# SparkFun_Artemis_OpenLog.net
KiCad netlist of a schematic drawn in EAGLE
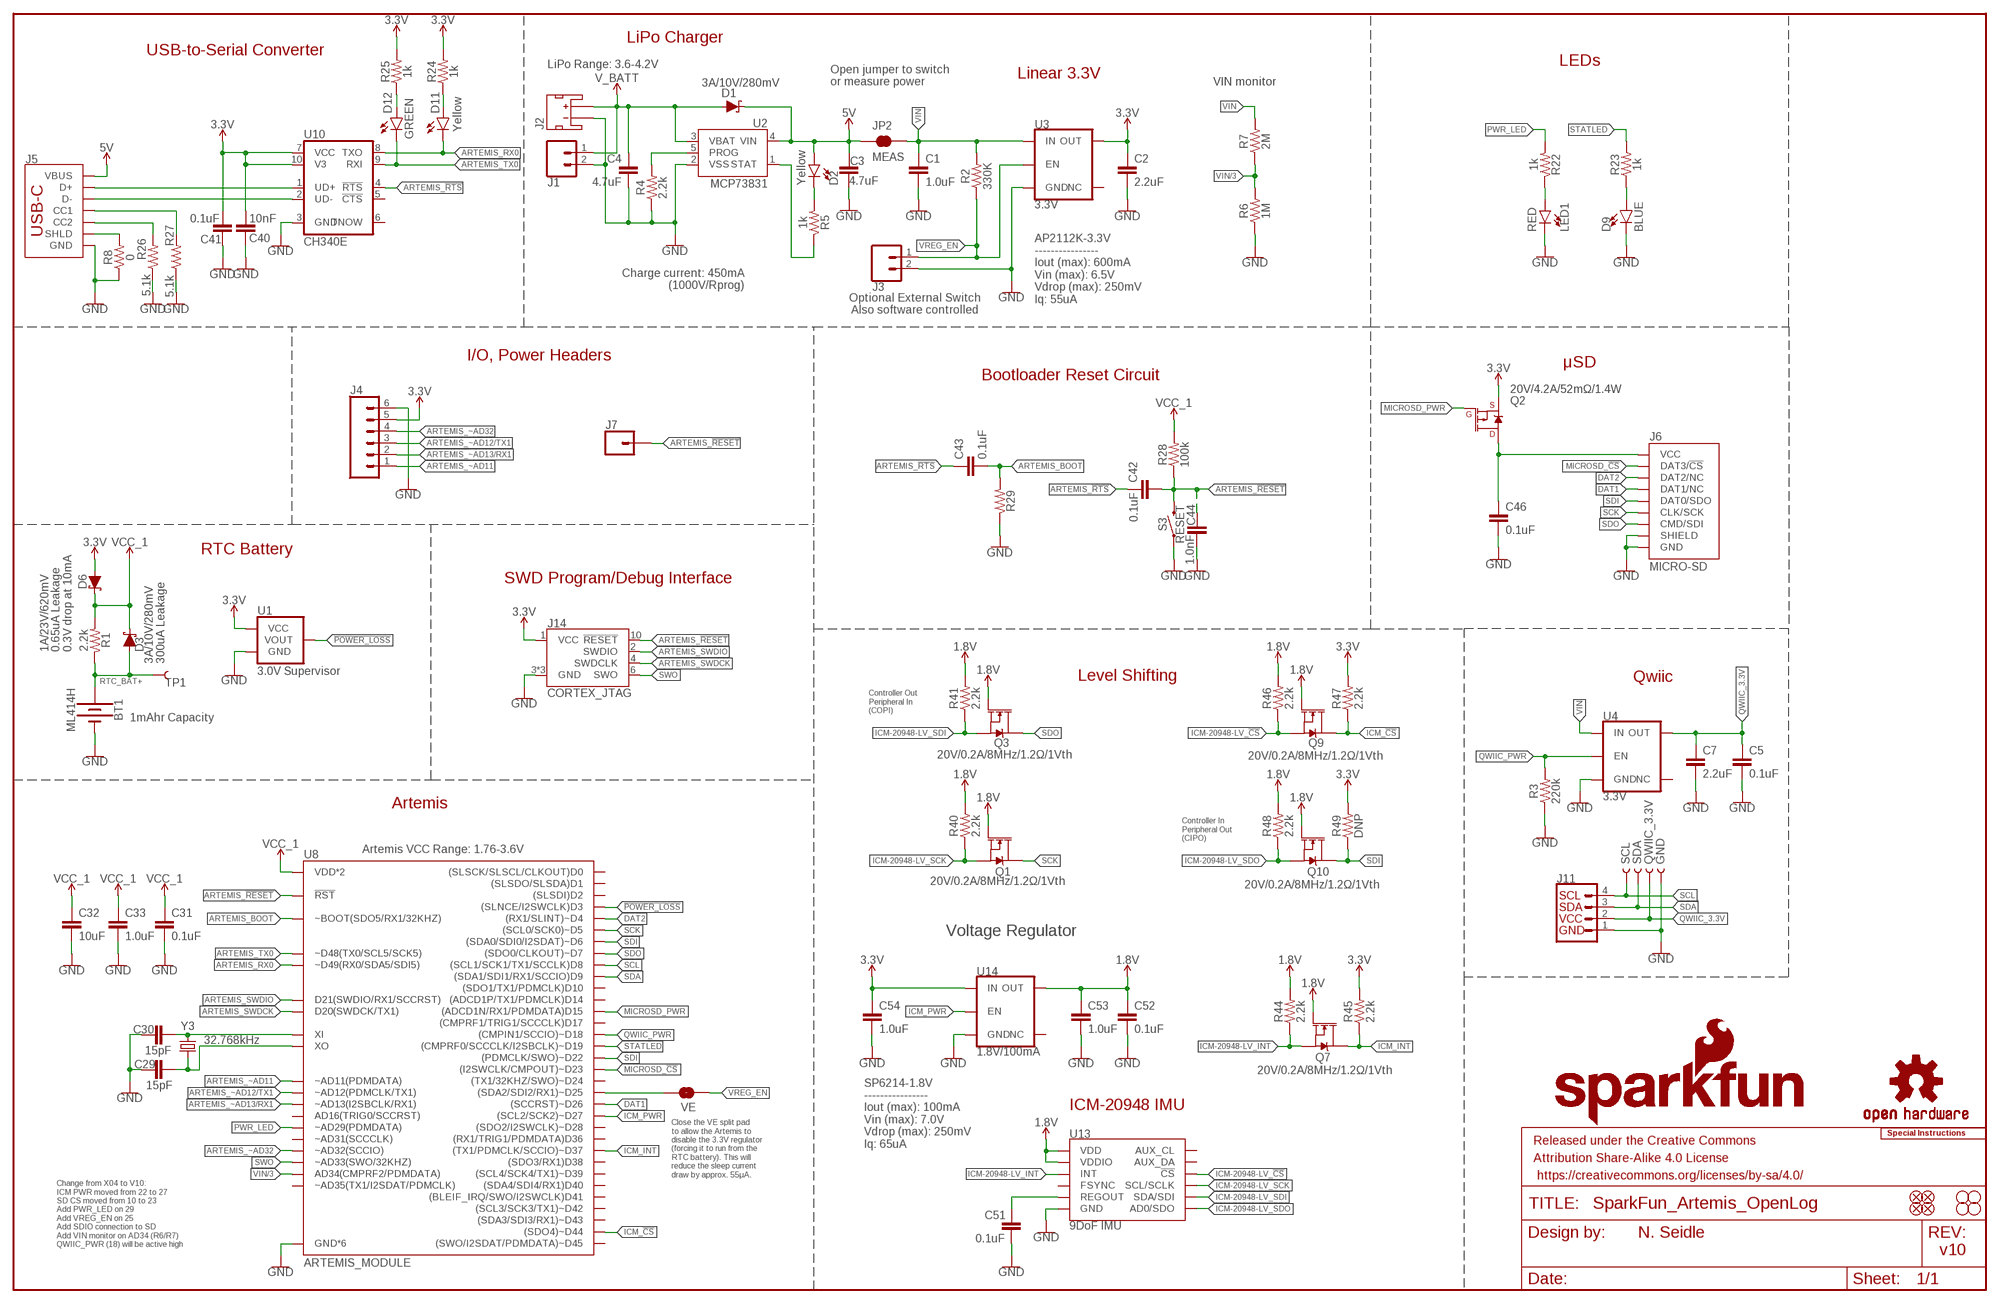
[diagram p0: schematic, sheet 1]

(export (version "E")
  (design (tool "Eeschema 10.0.6"))
  (components
    (comp (ref "BT1")
      (value "ML414H")
      (footprint "eagle-import:ML414H_IV01E")
      (libsource (lib "eagle-import") (part "ML414H_IV01E_BATTERY"))
    )
    (comp (ref "C1")
      (value "1.0uF")
      (footprint "eagle-import:0402-TIGHT")
      (libsource (lib "eagle-import") (part "1.0UF-0402T-16V-10%"))
    )
    (comp (ref "C2")
      (value "2.2uF")
      (footprint "eagle-import:0402-TIGHT")
      (libsource (lib "eagle-import") (part "2.2UF-0402_TIGHT-10V-10%-X5R"))
    )
    (comp (ref "C3")
      (value "4.7uF")
      (footprint "eagle-import:0402-TIGHT")
      (libsource (lib "eagle-import") (part "4.7UF-0402_TIGHT-6.3V-20%-X5R"))
    )
    (comp (ref "C4")
      (value "4.7uF")
      (footprint "eagle-import:0402-TIGHT")
      (libsource (lib "eagle-import") (part "4.7UF-0402_TIGHT-6.3V-20%-X5R"))
    )
    (comp (ref "C5")
      (value "0.1uF")
      (footprint "eagle-import:0402-TIGHT")
      (libsource (lib "eagle-import") (part "0.1UF-0402T-6.3V-10%-X7R"))
    )
    (comp (ref "C7")
      (value "2.2uF")
      (footprint "eagle-import:0402-TIGHT")
      (libsource (lib "eagle-import") (part "2.2UF-0402_TIGHT-10V-10%-X5R"))
    )
    (comp (ref "C29")
      (value "15pF")
      (footprint "eagle-import:0402-TIGHT")
      (libsource (lib "eagle-import") (part "15PF-0402T-50V-5%"))
    )
    (comp (ref "C30")
      (value "15pF")
      (footprint "eagle-import:0402-TIGHT")
      (libsource (lib "eagle-import") (part "15PF-0402T-50V-5%"))
    )
    (comp (ref "C31")
      (value "0.1uF")
      (footprint "eagle-import:0402-TIGHT")
      (libsource (lib "eagle-import") (part "0.1UF-0402T-16V-10%"))
    )
    (comp (ref "C32")
      (value "10uF")
      (footprint "eagle-import:0402-TIGHT")
      (libsource (lib "eagle-import") (part "10UF-0402T-6.3V-20%"))
    )
    (comp (ref "C33")
      (value "1.0uF")
      (footprint "eagle-import:0402-TIGHT")
      (libsource (lib "eagle-import") (part "1.0UF-0402T-16V-10%"))
    )
    (comp (ref "C40")
      (value "10nF")
      (footprint "eagle-import:0402-TIGHT")
      (libsource (lib "eagle-import") (part "10NF-0402T-25V-10%"))
    )
    (comp (ref "C41")
      (value "0.1uF")
      (footprint "eagle-import:0402-TIGHT")
      (libsource (lib "eagle-import") (part "0.1UF-0402T-16V-10%"))
    )
    (comp (ref "C42")
      (value "0.1uF")
      (footprint "eagle-import:0402-TIGHT")
      (libsource (lib "eagle-import") (part "0.1UF-0402T-16V-10%"))
    )
    (comp (ref "C43")
      (value "0.1uF")
      (footprint "eagle-import:0402-TIGHT")
      (libsource (lib "eagle-import") (part "0.1UF-0402T-16V-10%"))
    )
    (comp (ref "C44")
      (value "1.0nF")
      (footprint "eagle-import:0402-TIGHT")
      (libsource (lib "eagle-import") (part "1.0NF/1000PF-0402_TIGHT-50V-10%"))
    )
    (comp (ref "C46")
      (value "0.1uF")
      (footprint "eagle-import:0402-TIGHT")
      (libsource (lib "eagle-import") (part "0.1UF-0402T-16V-10%"))
    )
    (comp (ref "C51")
      (value "0.1uF")
      (footprint "eagle-import:0402-TIGHT")
      (libsource (lib "eagle-import") (part "0.1UF-0402T-16V-10%"))
    )
    (comp (ref "C52")
      (value "0.1uF")
      (footprint "eagle-import:0402-TIGHT")
      (libsource (lib "eagle-import") (part "0.1UF-0402T-16V-10%"))
    )
    (comp (ref "C53")
      (value "1.0uF")
      (footprint "eagle-import:0402-TIGHT")
      (libsource (lib "eagle-import") (part "1.0UF-0402T-16V-10%"))
    )
    (comp (ref "C54")
      (value "1.0uF")
      (footprint "eagle-import:0402-TIGHT")
      (libsource (lib "eagle-import") (part "1.0UF-0402T-16V-10%"))
    )
    (comp (ref "D1")
      (value "3A/10V/280mV")
      (footprint "eagle-import:SOD-323")
      (libsource (lib "eagle-import") (part "DIODE-SCHOTTKY-BAT60A"))
    )
    (comp (ref "D2")
      (value "Yellow")
      (footprint "eagle-import:LED-0603")
      (libsource (lib "eagle-import") (part "LED-YELLOW0603"))
    )
    (comp (ref "D3")
      (value "3A/10V/280mV")
      (footprint "eagle-import:SOD-323")
      (libsource (lib "eagle-import") (part "DIODE-SCHOTTKY-BAT60A"))
    )
    (comp (ref "D6")
      (value "1A/23V/620mV")
      (footprint "eagle-import:SOD-323")
      (libsource (lib "eagle-import") (part "DIODE-SCHOTTKY-BAT20J"))
    )
    (comp (ref "D9")
      (value "BLUE")
      (footprint "eagle-import:LED-0603")
      (libsource (lib "eagle-import") (part "LED-BLUE0603"))
    )
    (comp (ref "D11")
      (value "Yellow")
      (footprint "eagle-import:LED-0603")
      (libsource (lib "eagle-import") (part "LED-YELLOW0603"))
    )
    (comp (ref "D12")
      (value "GREEN")
      (footprint "eagle-import:LED-0603")
      (libsource (lib "eagle-import") (part "LED-GREEN0603"))
    )
    (comp (ref "FD1")
      (value "FIDUCIAL1X2")
      (footprint "eagle-import:FIDUCIAL-1X2")
      (libsource (lib "eagle-import") (part "FIDUCIAL1X2"))
    )
    (comp (ref "FD2")
      (value "FIDUCIAL1X2")
      (footprint "eagle-import:FIDUCIAL-1X2")
      (libsource (lib "eagle-import") (part "FIDUCIAL1X2"))
    )
    (comp (ref "FD3")
      (value "FIDUCIAL1X2")
      (footprint "eagle-import:FIDUCIAL-1X2")
      (libsource (lib "eagle-import") (part "FIDUCIAL1X2"))
    )
    (comp (ref "FD4")
      (value "FIDUCIAL1X2")
      (footprint "eagle-import:FIDUCIAL-1X2")
      (libsource (lib "eagle-import") (part "FIDUCIAL1X2"))
    )
    (comp (ref "FRAME1")
      (value "FRAME-LEDGER")
      (footprint "eagle-import:CREATIVE_COMMONS")
      (libsource (lib "eagle-import") (part "FRAME-LEDGER"))
    )
    (comp (ref "GND")
      (value "TEST-POINTTP_15TH_THRU")
      (footprint "eagle-import:TP_15TH")
      (libsource (lib "eagle-import") (part "TEST-POINTTP_15TH_THRU"))
    )
    (comp (ref "H1")
      (value "STAND-OFF")
      (footprint "eagle-import:STAND-OFF")
      (libsource (lib "eagle-import") (part "STAND-OFF"))
    )
    (comp (ref "H2")
      (value "STAND-OFF")
      (footprint "eagle-import:STAND-OFF")
      (libsource (lib "eagle-import") (part "STAND-OFF"))
    )
    (comp (ref "H3")
      (value "STAND-OFF")
      (footprint "eagle-import:STAND-OFF")
      (libsource (lib "eagle-import") (part "STAND-OFF"))
    )
    (comp (ref "H4")
      (value "STAND-OFF")
      (footprint "eagle-import:STAND-OFF")
      (libsource (lib "eagle-import") (part "STAND-OFF"))
    )
    (comp (ref "J1")
      (value "CONN_021X02_NO_SILK")
      (footprint "eagle-import:1X02_NO_SILK")
      (libsource (lib "eagle-import") (part "CONN_021X02_NO_SILK"))
    )
    (comp (ref "J2")
      (value "JST_2MM_MALE")
      (footprint "eagle-import:JST-2-SMD")
      (libsource (lib "eagle-import") (part "JST_2MM_MALE"))
    )
    (comp (ref "J3")
      (value "CONN_021X02_NO_SILK")
      (footprint "eagle-import:1X02_NO_SILK")
      (libsource (lib "eagle-import") (part "CONN_021X02_NO_SILK"))
    )
    (comp (ref "J4")
      (value "CONN_06NO_SILK_NO_POP")
      (footprint "eagle-import:1X06_NO_SILK")
      (libsource (lib "eagle-import") (part "CONN_06NO_SILK_NO_POP"))
    )
    (comp (ref "J5")
      (value "USB_C_4-LAYER_PADS")
      (footprint "eagle-import:USB-C-16P_4LAYER-PADS")
      (libsource (lib "eagle-import") (part "USB_C_4-LAYER_PADS"))
    )
    (comp (ref "J6")
      (value "MICRO-SD")
      (footprint "eagle-import:MICRO-SD-SOCKET")
      (libsource (lib "eagle-import") (part "MICRO-SD-SDIOPUSH-PUSH"))
    )
    (comp (ref "J7")
      (value "CONN_01PTH_NO_SILK_YES_STOP")
      (footprint "eagle-import:1X01_NO_SILK")
      (libsource (lib "eagle-import") (part "CONN_01PTH_NO_SILK_YES_STOP"))
    )
    (comp (ref "J11")
      (value "QWIIC_CONNECTORJS-1MM")
      (footprint "eagle-import:JST04_1MM_RA")
      (libsource (lib "eagle-import") (part "QWIIC_CONNECTORJS-1MM"))
    )
    (comp (ref "J14")
      (value "CORTEX_JTAG")
      (footprint "eagle-import:2X5-PTH-1.27MM")
      (libsource (lib "eagle-import") (part "CORTEX_JTAG_DEBUG_MINIMUM_PTH"))
    )
    (comp (ref "JP2")
      (value "MEAS")
      (footprint "eagle-import:COMBO-JUMPER_2_NC_TRACE")
      (libsource (lib "eagle-import") (part "JUMPER-COMBO_2_NC_TRACE"))
    )
    (comp (ref "LED1")
      (value "RED")
      (footprint "eagle-import:LED-0603")
      (libsource (lib "eagle-import") (part "LED-RED0603"))
    )
    (comp (ref "LOGO1")
      (value "SFE_LOGO_NAME.1_INCH")
      (footprint "eagle-import:SFE_LOGO_NAME_.1")
      (libsource (lib "eagle-import") (part "SFE_LOGO_NAME.1_INCH"))
    )
    (comp (ref "LOGO2")
      (value "OSHW-LOGOS")
      (footprint "eagle-import:OSHW-LOGO-S")
      (libsource (lib "eagle-import") (part "OSHW-LOGOS"))
    )
    (comp (ref "LOGO3")
      (value "SPECIAL_INSTRUCTIONS-ORDERING")
      (footprint "eagle-import:ORDERING_INSTRUCTIONS")
      (libsource (lib "eagle-import") (part "SPECIAL_INSTRUCTIONS-ORDERING"))
    )
    (comp (ref "LOGO4")
      (value "SFE_LOGO_FLAME.1_INCH")
      (footprint "eagle-import:SFE_LOGO_FLAME_.1")
      (libsource (lib "eagle-import") (part "SFE_LOGO_FLAME.1_INCH"))
    )
    (comp (ref "LOGO5")
      (value "SFE_LOGO_FLAME.1_INCH")
      (footprint "eagle-import:SFE_LOGO_FLAME_.1")
      (libsource (lib "eagle-import") (part "SFE_LOGO_FLAME.1_INCH"))
    )
    (comp (ref "Q1")
      (value "20V/0.2A/8MHz/1.2Ω/1Vth")
      (footprint "eagle-import:SOT-416FL")
      (libsource (lib "eagle-import") (part "MOSFET-NCH-RE1C00UNTL"))
    )
    (comp (ref "Q2")
      (value "20V/4.2A/52mΩ/1.4W")
      (footprint "eagle-import:SOT23-3")
      (libsource (lib "eagle-import") (part "MOSFET_PCH-DMG2305UX-7"))
    )
    (comp (ref "Q3")
      (value "20V/0.2A/8MHz/1.2Ω/1Vth")
      (footprint "eagle-import:SOT-416FL")
      (libsource (lib "eagle-import") (part "MOSFET-NCH-RE1C00UNTL"))
    )
    (comp (ref "Q7")
      (value "20V/0.2A/8MHz/1.2Ω/1Vth")
      (footprint "eagle-import:SOT-416FL")
      (libsource (lib "eagle-import") (part "MOSFET-NCH-RE1C00UNTL"))
    )
    (comp (ref "Q9")
      (value "20V/0.2A/8MHz/1.2Ω/1Vth")
      (footprint "eagle-import:SOT-416FL")
      (libsource (lib "eagle-import") (part "MOSFET-NCH-RE1C00UNTL"))
    )
    (comp (ref "Q10")
      (value "20V/0.2A/8MHz/1.2Ω/1Vth")
      (footprint "eagle-import:SOT-416FL")
      (libsource (lib "eagle-import") (part "MOSFET-NCH-RE1C00UNTL"))
    )
    (comp (ref "QWIIC_3.3V")
      (value "TEST-POINTTP_15TH_THRU")
      (footprint "eagle-import:TP_15TH")
      (libsource (lib "eagle-import") (part "TEST-POINTTP_15TH_THRU"))
    )
    (comp (ref "R1")
      (value "2.2k")
      (footprint "eagle-import:0402-TIGHT")
      (libsource (lib "eagle-import") (part "2.2KOHM-0402T-1/16W-1%"))
    )
    (comp (ref "R2")
      (value "330K")
      (footprint "eagle-import:0402-TIGHT")
      (libsource (lib "eagle-import") (part "330KOHM-0402T-1/16W-1%"))
    )
    (comp (ref "R3")
      (value "220k")
      (footprint "eagle-import:0402-TIGHT")
      (libsource (lib "eagle-import") (part "220KOHM-0402T-1/16W-1%"))
    )
    (comp (ref "R4")
      (value "2.2k")
      (footprint "eagle-import:0402-TIGHT")
      (libsource (lib "eagle-import") (part "2.2KOHM-0402T-1/16W-1%"))
    )
    (comp (ref "R5")
      (value "1k")
      (footprint "eagle-import:0402-TIGHT")
      (libsource (lib "eagle-import") (part "1KOHM-0402T-1/16W-1%"))
    )
    (comp (ref "R6")
      (value "1M")
      (footprint "eagle-import:0402-TIGHT")
      (libsource (lib "eagle-import") (part "1MOHM-0402T-1/16W-1%"))
    )
    (comp (ref "R7")
      (value "2M")
      (footprint "eagle-import:0402-TIGHT")
      (libsource (lib "eagle-import") (part "2MOHM-0402T-1/16W-1%"))
    )
    (comp (ref "R8")
      (value "0")
      (footprint "eagle-import:0402-TIGHT")
      (libsource (lib "eagle-import") (part "0OHM-0402T-1/10W"))
    )
    (comp (ref "R22")
      (value "1k")
      (footprint "eagle-import:0402-TIGHT")
      (libsource (lib "eagle-import") (part "1KOHM-0402T-1/16W-1%"))
    )
    (comp (ref "R23")
      (value "1k")
      (footprint "eagle-import:0402-TIGHT")
      (libsource (lib "eagle-import") (part "1KOHM-0402T-1/16W-1%"))
    )
    (comp (ref "R24")
      (value "1k")
      (footprint "eagle-import:0402-TIGHT")
      (libsource (lib "eagle-import") (part "1KOHM-0402T-1/16W-1%"))
    )
    (comp (ref "R25")
      (value "1k")
      (footprint "eagle-import:0402-TIGHT")
      (libsource (lib "eagle-import") (part "1KOHM-0402T-1/16W-1%"))
    )
    (comp (ref "R26")
      (value "5.1k")
      (footprint "eagle-import:0402-TIGHT")
      (libsource (lib "eagle-import") (part "5.1KOHM-0402T-1/16W-1%"))
    )
    (comp (ref "R27")
      (value "5.1k")
      (footprint "eagle-import:0402-TIGHT")
      (libsource (lib "eagle-import") (part "5.1KOHM-0402T-1/16W-1%"))
    )
    (comp (ref "R28")
      (value "100k")
      (footprint "eagle-import:0402-TIGHT")
      (libsource (lib "eagle-import") (part "100KOHM-0402T-1/16W-1%"))
    )
    (comp (ref "R29")
      (value "220KOHM-0402T-1/16W-1%")
      (footprint "eagle-import:0402-TIGHT")
      (libsource (lib "eagle-import") (part "220KOHM-0402T-1/16W-1%"))
    )
    (comp (ref "R40")
      (value "2.2k")
      (footprint "eagle-import:0402-TIGHT")
      (libsource (lib "eagle-import") (part "2.2KOHM-0402T-1/16W-1%"))
    )
    (comp (ref "R41")
      (value "2.2k")
      (footprint "eagle-import:0402-TIGHT")
      (libsource (lib "eagle-import") (part "2.2KOHM-0402T-1/16W-1%"))
    )
    (comp (ref "R44")
      (value "2.2k")
      (footprint "eagle-import:0402-TIGHT")
      (libsource (lib "eagle-import") (part "2.2KOHM-0402T-1/16W-1%"))
    )
    (comp (ref "R45")
      (value "2.2k")
      (footprint "eagle-import:0402-TIGHT")
      (libsource (lib "eagle-import") (part "2.2KOHM-0402T-1/16W-1%"))
    )
    (comp (ref "R46")
      (value "2.2k")
      (footprint "eagle-import:0402-TIGHT")
      (libsource (lib "eagle-import") (part "2.2KOHM-0402T-1/16W-1%"))
    )
    (comp (ref "R47")
      (value "2.2k")
      (footprint "eagle-import:0402-TIGHT")
      (libsource (lib "eagle-import") (part "2.2KOHM-0402T-1/16W-1%"))
    )
    (comp (ref "R48")
      (value "2.2k")
      (footprint "eagle-import:0402-TIGHT")
      (libsource (lib "eagle-import") (part "2.2KOHM-0402T-1/16W-1%"))
    )
    (comp (ref "R49")
      (value "DNP")
      (footprint "eagle-import:0402-TIGHT")
      (libsource (lib "eagle-import") (part "RESISTOR0402T"))
    )
    (comp (ref "S3")
      (value "RESET")
      (footprint "eagle-import:TACTILE_SWITCH_SMD_4.6X2.8MM")
      (libsource (lib "eagle-import") (part "MOMENTARY-SWITCH-SPST-SMD-4.6X2.8MM"))
    )
    (comp (ref "SCL")
      (value "TEST-POINTTP_15TH_THRU")
      (footprint "eagle-import:TP_15TH")
      (libsource (lib "eagle-import") (part "TEST-POINTTP_15TH_THRU"))
    )
    (comp (ref "SDA")
      (value "TEST-POINTTP_15TH_THRU")
      (footprint "eagle-import:TP_15TH")
      (libsource (lib "eagle-import") (part "TEST-POINTTP_15TH_THRU"))
    )
    (comp (ref "TP1")
      (value "TEST-POINT3")
      (footprint "eagle-import:PAD.03X.03")
      (libsource (lib "eagle-import") (part "TEST-POINT3"))
    )
    (comp (ref "U1")
      (value "3.0V Supervisor")
      (footprint "eagle-import:SOT23-3")
      (libsource (lib "eagle-import") (part "V_SUPERVISOR"))
    )
    (comp (ref "U2")
      (value "MCP73831")
      (footprint "eagle-import:SOT23-5")
      (libsource (lib "eagle-import") (part "MCP73831"))
    )
    (comp (ref "U3")
      (value "3.3V")
      (footprint "eagle-import:SOT23-5")
      (libsource (lib "eagle-import") (part "V_REG_AP2112K-3.3V"))
    )
    (comp (ref "U4")
      (value "3.3V")
      (footprint "eagle-import:SOT23-5")
      (libsource (lib "eagle-import") (part "V_REG_AP2112K-3.3V"))
    )
    (comp (ref "U8")
      (value "ARTEMIS_MODULE")
      (footprint "eagle-import:ARTEMIS_FP")
      (libsource (lib "eagle-import") (part "ARTEMIS_MODULESMD"))
    )
    (comp (ref "U10")
      (value "CH340E")
      (footprint "eagle-import:MSOP10")
      (libsource (lib "eagle-import") (part "CH340E_MSOP10"))
    )
    (comp (ref "U13")
      (value "9DoF IMU")
      (footprint "eagle-import:QFN24-3X3-ICM-20948")
      (libsource (lib "eagle-import") (part "ICM-20948"))
    )
    (comp (ref "U14")
      (value "1.8V/100mA")
      (footprint "eagle-import:SC70")
      (libsource (lib "eagle-import") (part "V_REG_SP6214-1.8V"))
    )
    (comp (ref "VE")
      (value "JUMPER-SMT_2_NO_SILK")
      (footprint "eagle-import:SMT-JUMPER_2_NO_SILK")
      (libsource (lib "eagle-import") (part "JUMPER-SMT_2_NO_SILK"))
    )
    (comp (ref "Y3")
      (value "32.768kHz")
      (footprint "eagle-import:CRYSTAL-SMD-3.2X1.5MM")
      (libsource (lib "eagle-import") (part "CRYSTAL-32.768KHZSMD-3.2X1.5"))
    )
  )
  (nets
    (net (code "1") (name "/ARTEMIS_~{AD11}") (class "Default")
      (node (ref "J4") (pin "1") (pinfunction "1_1") (pintype "passive"))
      (node (ref "U8") (pin "~AD11") (pinfunction "~{AD11(PDMDATA})_~AD11") (pintype "bidirectional"))
    )
    (net (code "2") (name "/ARTEMIS_~{AD12{slash}TX1}") (class "Default")
      (node (ref "J4") (pin "3") (pinfunction "3_3") (pintype "passive"))
      (node (ref "U8") (pin "~AD12") (pinfunction "~{AD12(PDMCLK/TX1})_~AD12") (pintype "bidirectional"))
    )
    (net (code "3") (name "/ARTEMIS_~{AD13{slash}RX1}") (class "Default")
      (node (ref "J4") (pin "2") (pinfunction "2_2") (pintype "passive"))
      (node (ref "U8") (pin "~AD13") (pinfunction "~{AD13(I2SBCLK/RX1})_~AD13") (pintype "bidirectional"))
    )
    (net (code "4") (name "/ARTEMIS_~{AD32}") (class "Default")
      (node (ref "J4") (pin "4") (pinfunction "4_4") (pintype "passive"))
      (node (ref "U8") (pin "~AD32") (pinfunction "~{AD32(SCCIO})_~AD32") (pintype "bidirectional"))
    )
    (net (code "5") (name "/ARTEMIS_~{RESET}") (class "Default")
      (node (ref "C42") (pin "2") (pinfunction "2_2") (pintype "passive"))
      (node (ref "C44") (pin "1") (pinfunction "1_1") (pintype "passive"))
      (node (ref "J14") (pin "10") (pinfunction "~{RESET}_10") (pintype "bidirectional"))
      (node (ref "J7") (pin "1") (pinfunction "1_1") (pintype "passive"))
      (node (ref "R28") (pin "1") (pinfunction "1_1") (pintype "passive"))
      (node (ref "S3") (pin "3") (pinfunction "2_3") (pintype "passive"))
      (node (ref "S3") (pin "4") (pinfunction "2_4") (pintype "passive"))
      (node (ref "U8") (pin "~RST") (pinfunction "~{RST}_~RST") (pintype "bidirectional"))
    )
    (net (code "6") (name "/ARTEMIS_~{RTS}") (class "Default")
      (node (ref "C42") (pin "1") (pinfunction "1_1") (pintype "passive"))
      (node (ref "C43") (pin "1") (pinfunction "1_1") (pintype "passive"))
      (node (ref "U10") (pin "4") (pinfunction "~{RTS}_4") (pintype "bidirectional"))
    )
    (net (code "7") (name "/ICM-20948-LV_~{CS}") (class "Default")
      (node (ref "Q9") (pin "2") (pinfunction "S_2") (pintype "bidirectional"))
      (node (ref "R46") (pin "1") (pinfunction "1_1") (pintype "passive"))
      (node (ref "U13") (pin "22") (pinfunction "~{CS}_22") (pintype "bidirectional"))
    )
    (net (code "8") (name "/ICM_~{CS}") (class "Default")
      (node (ref "Q9") (pin "3") (pinfunction "D_3") (pintype "bidirectional"))
      (node (ref "R47") (pin "1") (pinfunction "1_1") (pintype "passive"))
      (node (ref "U8") (pin "~D44") (pinfunction "(SDO4)~{D44}_~D44") (pintype "bidirectional"))
    )
    (net (code "9") (name "/MICROSD_~{CS}") (class "Default")
      (node (ref "J6") (pin "CS/DAT3") (pinfunction "DAT3/~{CS}_CS/DAT3") (pintype "bidirectional"))
      (node (ref "U8") (pin "~D23") (pinfunction "(I2SWCLK/CMPOUT)~{D23}_~D23") (pintype "bidirectional"))
    )
    (net (code "10") (name "/RTC_BAT+") (class "Default")
      (node (ref "BT1") (pin "+") (pinfunction "+_+") (pintype "power_in"))
      (node (ref "D3") (pin "A") (pinfunction "A_A") (pintype "passive"))
      (node (ref "R1") (pin "1") (pinfunction "1_1") (pintype "passive"))
      (node (ref "TP1") (pin "P$1") (pinfunction "1_P$1") (pintype "bidirectional"))
    )
    (net (code "11") (name "/~{POWER_LOSS}") (class "Default")
      (node (ref "U1") (pin "2") (pinfunction "VOUT_2") (pintype "output"))
      (node (ref "U8") (pin "D3") (pinfunction "(SLNCE/I2SWCLK)D3_D3") (pintype "bidirectional"))
    )
    (net (code "12") (name "1.8V") (class "Default")
      (node (ref "C52") (pin "1") (pinfunction "1_1") (pintype "passive"))
      (node (ref "C53") (pin "1") (pinfunction "1_1") (pintype "passive"))
      (node (ref "Q1") (pin "1") (pinfunction "G_1") (pintype "bidirectional"))
      (node (ref "Q10") (pin "1") (pinfunction "G_1") (pintype "bidirectional"))
      (node (ref "Q3") (pin "1") (pinfunction "G_1") (pintype "bidirectional"))
      (node (ref "Q7") (pin "1") (pinfunction "G_1") (pintype "bidirectional"))
      (node (ref "Q9") (pin "1") (pinfunction "G_1") (pintype "bidirectional"))
      (node (ref "R40") (pin "2") (pinfunction "2_2") (pintype "passive"))
      (node (ref "R41") (pin "2") (pinfunction "2_2") (pintype "passive"))
      (node (ref "R44") (pin "2") (pinfunction "2_2") (pintype "passive"))
      (node (ref "R46") (pin "2") (pinfunction "2_2") (pintype "passive"))
      (node (ref "R48") (pin "2") (pinfunction "2_2") (pintype "passive"))
      (node (ref "U13") (pin "13") (pinfunction "VDD_13") (pintype "bidirectional"))
      (node (ref "U13") (pin "8") (pinfunction "VDDIO_8") (pintype "bidirectional"))
      (node (ref "U14") (pin "5") (pinfunction "OUT_5") (pintype "passive"))
    )
    (net (code "13") (name "3.3V") (class "Default")
      (node (ref "C2") (pin "1") (pinfunction "1_1") (pintype "passive"))
      (node (ref "C40") (pin "1") (pinfunction "1_1") (pintype "passive"))
      (node (ref "C41") (pin "1") (pinfunction "1_1") (pintype "passive"))
      (node (ref "C54") (pin "1") (pinfunction "1_1") (pintype "passive"))
      (node (ref "D6") (pin "A") (pinfunction "A_A") (pintype "passive"))
      (node (ref "J14") (pin "1") (pinfunction "VCC_1") (pintype "bidirectional"))
      (node (ref "J4") (pin "5") (pinfunction "5_5") (pintype "passive"))
      (node (ref "Q2") (pin "2") (pinfunction "S_2") (pintype "bidirectional"))
      (node (ref "R24") (pin "2") (pinfunction "2_2") (pintype "passive"))
      (node (ref "R25") (pin "2") (pinfunction "2_2") (pintype "passive"))
      (node (ref "R45") (pin "2") (pinfunction "2_2") (pintype "passive"))
      (node (ref "R47") (pin "2") (pinfunction "2_2") (pintype "passive"))
      (node (ref "R49") (pin "2") (pinfunction "2_2") (pintype "passive"))
      (node (ref "U1") (pin "3") (pinfunction "VCC_3") (pintype "input"))
      (node (ref "U10") (pin "10") (pinfunction "V3_10") (pintype "bidirectional"))
      (node (ref "U10") (pin "7") (pinfunction "VCC_7") (pintype "bidirectional"))
      (node (ref "U14") (pin "1") (pinfunction "IN_1") (pintype "input"))
      (node (ref "U3") (pin "5") (pinfunction "OUT_5") (pintype "passive"))
    )
    (net (code "14") (name "5V") (class "Default")
      (node (ref "C3") (pin "1") (pinfunction "1_1") (pintype "passive"))
      (node (ref "D1") (pin "C") (pinfunction "C_C") (pintype "passive"))
      (node (ref "D2") (pin "A") (pinfunction "A_A") (pintype "passive"))
      (node (ref "J5") (pin "VBUS1") (pinfunction "VBUS_VBUS1") (pintype "bidirectional"))
      (node (ref "J5") (pin "VBUS2") (pinfunction "VBUS_VBUS2") (pintype "bidirectional"))
      (node (ref "JP2") (pin "1") (pinfunction "1_1") (pintype "passive"))
      (node (ref "JP2") (pin "3") (pinfunction "1_3") (pintype "passive"))
      (node (ref "U2") (pin "4") (pinfunction "VIN_4") (pintype "power_in"))
    )
    (net (code "15") (name "ARTEMIS_BOOT") (class "Default")
      (node (ref "C43") (pin "2") (pinfunction "2_2") (pintype "passive"))
      (node (ref "R29") (pin "2") (pinfunction "2_2") (pintype "passive"))
      (node (ref "U8") (pin "BOOT") (pinfunction "~{BOOT(SDO5/RX1/32KHZ})_BOOT") (pintype "bidirectional"))
    )
    (net (code "16") (name "ARTEMIS_RX0") (class "Default")
      (node (ref "D11") (pin "C") (pinfunction "C_C") (pintype "passive"))
      (node (ref "U10") (pin "8") (pinfunction "TXO_8") (pintype "bidirectional"))
      (node (ref "U8") (pin "RXI-0") (pinfunction "~{D49(RX0/SDA5/SDI5})_RXI-0") (pintype "bidirectional"))
    )
    (net (code "17") (name "ARTEMIS_SWDCK") (class "Default")
      (node (ref "J14") (pin "4") (pinfunction "SWDCLK_4") (pintype "bidirectional"))
      (node (ref "U8") (pin "SWDCK") (pinfunction "D20(SWDCK/TX1)_SWDCK") (pintype "bidirectional"))
    )
    (net (code "18") (name "ARTEMIS_SWDIO") (class "Default")
      (node (ref "J14") (pin "2") (pinfunction "SWDIO_2") (pintype "bidirectional"))
      (node (ref "U8") (pin "SWDIO") (pinfunction "D21(SWDIO/RX1/SCCRST)_SWDIO") (pintype "bidirectional"))
    )
    (net (code "19") (name "ARTEMIS_TX0") (class "Default")
      (node (ref "D12") (pin "C") (pinfunction "C_C") (pintype "passive"))
      (node (ref "U10") (pin "9") (pinfunction "RXI_9") (pintype "bidirectional"))
      (node (ref "U8") (pin "TXO-0") (pinfunction "~{D48(TX0/SCL5/SCK5})_TXO-0") (pintype "bidirectional"))
    )
    (net (code "20") (name "DAT1") (class "Default")
      (node (ref "J6") (pin "DAT1") (pinfunction "DAT1/NC_DAT1") (pintype "bidirectional"))
      (node (ref "U8") (pin "~D26") (pinfunction "(SCCRST)~{D26}_~D26") (pintype "bidirectional"))
    )
    (net (code "21") (name "DAT2") (class "Default")
      (node (ref "J6") (pin "DAT2") (pinfunction "DAT2/NC_DAT2") (pintype "bidirectional"))
      (node (ref "U8") (pin "~D4") (pinfunction "(RX1/SLINT)~{D4}_~D4") (pintype "bidirectional"))
    )
    (net (code "22") (name "GND") (class "Default")
      (node (ref "BT1") (pin "-") (pinfunction "-_-") (pintype "power_in"))
      (node (ref "C1") (pin "2") (pinfunction "2_2") (pintype "passive"))
      (node (ref "C2") (pin "2") (pinfunction "2_2") (pintype "passive"))
      (node (ref "C29") (pin "1") (pinfunction "1_1") (pintype "passive"))
      (node (ref "C3") (pin "2") (pinfunction "2_2") (pintype "passive"))
      (node (ref "C30") (pin "1") (pinfunction "1_1") (pintype "passive"))
      (node (ref "C31") (pin "1") (pinfunction "1_1") (pintype "passive"))
      (node (ref "C32") (pin "2") (pinfunction "2_2") (pintype "passive"))
      (node (ref "C33") (pin "2") (pinfunction "2_2") (pintype "passive"))
      (node (ref "C4") (pin "2") (pinfunction "2_2") (pintype "passive"))
      (node (ref "C40") (pin "2") (pinfunction "2_2") (pintype "passive"))
      (node (ref "C41") (pin "2") (pinfunction "2_2") (pintype "passive"))
      (node (ref "C44") (pin "2") (pinfunction "2_2") (pintype "passive"))
      (node (ref "C46") (pin "2") (pinfunction "2_2") (pintype "passive"))
      (node (ref "C5") (pin "2") (pinfunction "2_2") (pintype "passive"))
      (node (ref "C51") (pin "2") (pinfunction "2_2") (pintype "passive"))
      (node (ref "C52") (pin "2") (pinfunction "2_2") (pintype "passive"))
      (node (ref "C53") (pin "2") (pinfunction "2_2") (pintype "passive"))
      (node (ref "C54") (pin "2") (pinfunction "2_2") (pintype "passive"))
      (node (ref "C7") (pin "2") (pinfunction "2_2") (pintype "passive"))
      (node (ref "D9") (pin "C") (pinfunction "C_C") (pintype "passive"))
      (node (ref "GND") (pin "P$1") (pinfunction "1_P$1") (pintype "bidirectional"))
      (node (ref "J1") (pin "2") (pinfunction "2_2") (pintype "passive"))
      (node (ref "J11") (pin "1") (pinfunction "1_1") (pintype "power_in"))
      (node (ref "J14") (pin "3") (pinfunction "GND_3") (pintype "bidirectional"))
      (node (ref "J14") (pin "5") (pinfunction "GND_5") (pintype "bidirectional"))
      (node (ref "J14") (pin "9") (pinfunction "GND_9") (pintype "bidirectional"))
      (node (ref "J2") (pin "1") (pinfunction "-_1") (pintype "bidirectional"))
      (node (ref "J3") (pin "2") (pinfunction "2_2") (pintype "passive"))
      (node (ref "J4") (pin "6") (pinfunction "6_6") (pintype "passive"))
      (node (ref "J5") (pin "GND") (pinfunction "GND_GND") (pintype "bidirectional"))
      (node (ref "J5") (pin "GND2") (pinfunction "GND_GND2") (pintype "bidirectional"))
      (node (ref "J6") (pin "CD1") (pinfunction "SHIELD_CD1") (pintype "bidirectional"))
      (node (ref "J6") (pin "GND") (pinfunction "GND_GND") (pintype "bidirectional"))
      (node (ref "J6") (pin "GND1") (pinfunction "GND_GND1") (pintype "bidirectional"))
      (node (ref "J6") (pin "GND3") (pinfunction "GND_GND3") (pintype "bidirectional"))
      (node (ref "LED1") (pin "C") (pinfunction "C_C") (pintype "passive"))
      (node (ref "R26") (pin "1") (pinfunction "1_1") (pintype "passive"))
      (node (ref "R27") (pin "1") (pinfunction "1_1") (pintype "passive"))
      (node (ref "R29") (pin "1") (pinfunction "1_1") (pintype "passive"))
      (node (ref "R3") (pin "1") (pinfunction "1_1") (pintype "passive"))
      (node (ref "R4") (pin "1") (pinfunction "1_1") (pintype "passive"))
      (node (ref "R6") (pin "1") (pinfunction "1_1") (pintype "passive"))
      (node (ref "R8") (pin "1") (pinfunction "1_1") (pintype "passive"))
      (node (ref "S3") (pin "1") (pinfunction "1_1") (pintype "passive"))
      (node (ref "S3") (pin "2") (pinfunction "1_2") (pintype "passive"))
      (node (ref "U1") (pin "1") (pinfunction "GND_1") (pintype "input"))
      (node (ref "U10") (pin "3") (pinfunction "GND_3") (pintype "bidirectional"))
      (node (ref "U13") (pin "18") (pinfunction "GND_18") (pintype "bidirectional"))
      (node (ref "U13") (pin "20") (pinfunction "GND_20") (pintype "bidirectional"))
      (node (ref "U14") (pin "2") (pinfunction "GND_2") (pintype "input"))
      (node (ref "U2") (pin "2") (pinfunction "VSS_2") (pintype "power_in"))
      (node (ref "U3") (pin "2") (pinfunction "GND_2") (pintype "input"))
      (node (ref "U4") (pin "2") (pinfunction "GND_2") (pintype "input"))
      (node (ref "U8") (pin "GND@1") (pinfunction "GND*6_GND@1") (pintype "bidirectional"))
      (node (ref "U8") (pin "GND@22") (pinfunction "GND*6_GND@22") (pintype "bidirectional"))
      (node (ref "U8") (pin "GND@38") (pinfunction "GND*6_GND@38") (pintype "bidirectional"))
      (node (ref "U8") (pin "GND@39") (pinfunction "GND*6_GND@39") (pintype "bidirectional"))
      (node (ref "U8") (pin "GND@47") (pinfunction "GND*6_GND@47") (pintype "bidirectional"))
      (node (ref "U8") (pin "GND@59") (pinfunction "GND*6_GND@59") (pintype "bidirectional"))
    )
    (net (code "23") (name "ICM-20948-LV_INT") (class "Default")
      (node (ref "Q7") (pin "2") (pinfunction "S_2") (pintype "bidirectional"))
      (node (ref "R44") (pin "1") (pinfunction "1_1") (pintype "passive"))
      (node (ref "U13") (pin "12") (pinfunction "INT_12") (pintype "bidirectional"))
    )
    (net (code "24") (name "ICM-20948-LV_SCK") (class "Default")
      (node (ref "Q1") (pin "2") (pinfunction "S_2") (pintype "bidirectional"))
      (node (ref "R40") (pin "1") (pinfunction "1_1") (pintype "passive"))
      (node (ref "U13") (pin "23") (pinfunction "SCL/SCLK_23") (pintype "bidirectional"))
    )
    (net (code "25") (name "ICM-20948-LV_SDI") (class "Default")
      (node (ref "Q3") (pin "2") (pinfunction "S_2") (pintype "bidirectional"))
      (node (ref "R41") (pin "1") (pinfunction "1_1") (pintype "passive"))
      (node (ref "U13") (pin "24") (pinfunction "SDA/SDI_24") (pintype "bidirectional"))
    )
    (net (code "26") (name "ICM-20948-LV_SDO") (class "Default")
      (node (ref "Q10") (pin "2") (pinfunction "S_2") (pintype "bidirectional"))
      (node (ref "R48") (pin "1") (pinfunction "1_1") (pintype "passive"))
      (node (ref "U13") (pin "9") (pinfunction "AD0/SDO_9") (pintype "bidirectional"))
    )
    (net (code "27") (name "ICM_INT") (class "Default")
      (node (ref "Q7") (pin "3") (pinfunction "D_3") (pintype "bidirectional"))
      (node (ref "R45") (pin "1") (pinfunction "1_1") (pintype "passive"))
      (node (ref "U8") (pin "~D37") (pinfunction "(TX1/PDMCLK/SCCIO)~{D37}_~D37") (pintype "bidirectional"))
    )
    (net (code "28") (name "ICM_PWR") (class "Default")
      (node (ref "U14") (pin "3") (pinfunction "EN_3") (pintype "input"))
      (node (ref "U8") (pin "~D27") (pinfunction "(SCL2/SCK2)~{D27}_~D27") (pintype "bidirectional"))
    )
    (net (code "29") (name "MICROSD_PWR") (class "Default")
      (node (ref "Q2") (pin "1") (pinfunction "G_1") (pintype "bidirectional"))
      (node (ref "U8") (pin "D15") (pinfunction "(ADCD1N/RX1/PDMDATA)D15_D15") (pintype "bidirectional"))
    )
    (net (code "30") (name "Net-(D2-PadC)") (class "Default")
      (node (ref "D2") (pin "C") (pinfunction "C_C") (pintype "passive"))
      (node (ref "R5") (pin "2") (pinfunction "2_2") (pintype "passive"))
    )
    (net (code "31") (name "Net-(D9-PadA)") (class "Default")
      (node (ref "D9") (pin "A") (pinfunction "A_A") (pintype "passive"))
      (node (ref "R23") (pin "1") (pinfunction "1_1") (pintype "passive"))
    )
    (net (code "32") (name "Net-(D11-PadA)") (class "Default")
      (node (ref "D11") (pin "A") (pinfunction "A_A") (pintype "passive"))
      (node (ref "R24") (pin "1") (pinfunction "1_1") (pintype "passive"))
    )
    (net (code "33") (name "Net-(D12-PadA)") (class "Default")
      (node (ref "D12") (pin "A") (pinfunction "A_A") (pintype "passive"))
      (node (ref "R25") (pin "1") (pinfunction "1_1") (pintype "passive"))
    )
    (net (code "34") (name "Net-(J5-CC1)") (class "Default")
      (node (ref "J5") (pin "A5") (pinfunction "CC1_A5") (pintype "bidirectional"))
      (node (ref "R27") (pin "2") (pinfunction "2_2") (pintype "passive"))
    )
    (net (code "35") (name "Net-(J5-CC2)") (class "Default")
      (node (ref "J5") (pin "B5") (pinfunction "CC2_B5") (pintype "bidirectional"))
      (node (ref "R26") (pin "2") (pinfunction "2_2") (pintype "passive"))
    )
    (net (code "36") (name "Net-(J5-SHLD-PadSHLD1)") (class "Default")
      (node (ref "J5") (pin "SHLD1") (pinfunction "SHLD_SHLD1") (pintype "bidirectional"))
      (node (ref "J5") (pin "SHLD2") (pinfunction "SHLD_SHLD2") (pintype "bidirectional"))
      (node (ref "J5") (pin "SHLD3") (pinfunction "SHLD_SHLD3") (pintype "bidirectional"))
      (node (ref "J5") (pin "SHLD4") (pinfunction "SHLD_SHLD4") (pintype "bidirectional"))
      (node (ref "R8") (pin "2") (pinfunction "2_2") (pintype "passive"))
    )
    (net (code "37") (name "Net-(LED1-PadA)") (class "Default")
      (node (ref "LED1") (pin "A") (pinfunction "A_A") (pintype "passive"))
      (node (ref "R22") (pin "1") (pinfunction "1_1") (pintype "passive"))
    )
    (net (code "38") (name "Net-(Q2-D)") (class "Default")
      (node (ref "C46") (pin "1") (pinfunction "1_1") (pintype "passive"))
      (node (ref "J6") (pin "VCC") (pinfunction "VCC_VCC") (pintype "bidirectional"))
      (node (ref "Q2") (pin "3") (pinfunction "D_3") (pintype "bidirectional"))
    )
    (net (code "39") (name "Net-(U2-PROG)") (class "Default")
      (node (ref "R4") (pin "2") (pinfunction "2_2") (pintype "passive"))
      (node (ref "U2") (pin "5") (pinfunction "PROG_5") (pintype "input"))
    )
    (net (code "40") (name "Net-(U2-STAT)") (class "Default")
      (node (ref "R5") (pin "1") (pinfunction "1_1") (pintype "passive"))
      (node (ref "U2") (pin "1") (pinfunction "STAT_1") (pintype "output"))
    )
    (net (code "41") (name "Net-(U8-(SDA2{slash}SDI2{slash}RX1)~{D25})") (class "Default")
      (node (ref "U8") (pin "~D25") (pinfunction "(SDA2/SDI2/RX1)~{D25}_~D25") (pintype "bidirectional"))
      (node (ref "VE") (pin "1") (pinfunction "1_1") (pintype "passive"))
    )
    (net (code "42") (name "Net-(U10-UD+)") (class "Default")
      (node (ref "J5") (pin "A6") (pinfunction "D+_A6") (pintype "bidirectional"))
      (node (ref "J5") (pin "B6") (pinfunction "D+_B6") (pintype "bidirectional"))
      (node (ref "U10") (pin "1") (pinfunction "UD+_1") (pintype "bidirectional"))
    )
    (net (code "43") (name "Net-(U10-UD-)") (class "Default")
      (node (ref "J5") (pin "A7") (pinfunction "D-_A7") (pintype "bidirectional"))
      (node (ref "J5") (pin "B7") (pinfunction "D-_B7") (pintype "bidirectional"))
      (node (ref "U10") (pin "2") (pinfunction "UD-_2") (pintype "bidirectional"))
    )
    (net (code "44") (name "Net-(U13-REGOUT)") (class "Default")
      (node (ref "C51") (pin "1") (pinfunction "1_1") (pintype "passive"))
      (node (ref "U13") (pin "10") (pinfunction "REGOUT_10") (pintype "bidirectional"))
    )
    (net (code "45") (name "Net-(Y3-1)") (class "Default")
      (node (ref "C30") (pin "2") (pinfunction "2_2") (pintype "passive"))
      (node (ref "U8") (pin "XI") (pinfunction "XI_XI") (pintype "bidirectional"))
      (node (ref "Y3") (pin "P$1") (pinfunction "1_P$1") (pintype "passive"))
    )
    (net (code "46") (name "Net-(Y3-2)") (class "Default")
      (node (ref "C29") (pin "2") (pinfunction "2_2") (pintype "passive"))
      (node (ref "U8") (pin "XO") (pinfunction "XO_XO") (pintype "bidirectional"))
      (node (ref "Y3") (pin "P$2") (pinfunction "2_P$2") (pintype "passive"))
    )
    (net (code "47") (name "PWR_LED") (class "Default")
      (node (ref "R22") (pin "2") (pinfunction "2_2") (pintype "passive"))
      (node (ref "U8") (pin "~AD29") (pinfunction "~{AD29(PDMDATA})_~AD29") (pintype "bidirectional"))
    )
    (net (code "48") (name "QWIIC_3.3V") (class "Default")
      (node (ref "C5") (pin "1") (pinfunction "1_1") (pintype "passive"))
      (node (ref "C7") (pin "1") (pinfunction "1_1") (pintype "passive"))
      (node (ref "J11") (pin "2") (pinfunction "2_2") (pintype "power_in"))
      (node (ref "QWIIC_3.3V") (pin "P$1") (pinfunction "1_P$1") (pintype "bidirectional"))
      (node (ref "U4") (pin "5") (pinfunction "OUT_5") (pintype "passive"))
    )
    (net (code "49") (name "QWIIC_PWR") (class "Default")
      (node (ref "R3") (pin "2") (pinfunction "2_2") (pintype "passive"))
      (node (ref "U4") (pin "3") (pinfunction "EN_3") (pintype "input"))
      (node (ref "U8") (pin "~D18") (pinfunction "(CMPIN1/SCCIO)~{D18}_~D18") (pintype "bidirectional"))
    )
    (net (code "50") (name "SCK") (class "Default")
      (node (ref "J6") (pin "SCLK") (pinfunction "CLK/SCK_SCLK") (pintype "bidirectional"))
      (node (ref "Q1") (pin "3") (pinfunction "D_3") (pintype "bidirectional"))
      (node (ref "U8") (pin "~D5") (pinfunction "(SCL0/SCK0)~{D5}_~D5") (pintype "bidirectional"))
    )
    (net (code "51") (name "SCL") (class "Default")
      (node (ref "J11") (pin "4") (pinfunction "4_4") (pintype "passive"))
      (node (ref "SCL") (pin "P$1") (pinfunction "1_P$1") (pintype "bidirectional"))
      (node (ref "U8") (pin "D8") (pinfunction "(SCL1/SCK1/TX1/SCCLK)D8_D8") (pintype "bidirectional"))
    )
    (net (code "52") (name "SDA") (class "Default")
      (node (ref "J11") (pin "3") (pinfunction "3_3") (pintype "passive"))
      (node (ref "SDA") (pin "P$1") (pinfunction "1_P$1") (pintype "bidirectional"))
      (node (ref "U8") (pin "D9") (pinfunction "(SDA1/SDI1/RX1/SCCIO)D9_D9") (pintype "bidirectional"))
    )
    (net (code "53") (name "SDI") (class "Default")
      (node (ref "J6") (pin "DO/DAT0") (pinfunction "DAT0/SDO_DO/DAT0") (pintype "bidirectional"))
      (node (ref "Q10") (pin "3") (pinfunction "D_3") (pintype "bidirectional"))
      (node (ref "R49") (pin "1") (pinfunction "1_1") (pintype "passive"))
      (node (ref "U8") (pin "~D22") (pinfunction "(PDMCLK/SWO)~{D22}_~D22") (pintype "bidirectional"))
      (node (ref "U8") (pin "~D6") (pinfunction "(SDA0/SDI0/I2SDAT)~{D6}_~D6") (pintype "bidirectional"))
    )
    (net (code "54") (name "SDO") (class "Default")
      (node (ref "J6") (pin "DI/CMD") (pinfunction "CMD/SDI_DI/CMD") (pintype "bidirectional"))
      (node (ref "Q3") (pin "3") (pinfunction "D_3") (pintype "bidirectional"))
      (node (ref "U8") (pin "D7") (pinfunction "(SDO0/CLKOUT)~{D7}_D7") (pintype "bidirectional"))
    )
    (net (code "55") (name "STATLED") (class "Default")
      (node (ref "R23") (pin "2") (pinfunction "2_2") (pintype "passive"))
      (node (ref "U8") (pin "~D19") (pinfunction "(CMPRF0/SCCCLK/I2SBCLK)~{D19}_~D19") (pintype "bidirectional"))
    )
    (net (code "56") (name "SWO") (class "Default")
      (node (ref "J14") (pin "6") (pinfunction "SWO_6") (pintype "bidirectional"))
      (node (ref "U8") (pin "~AD33/SWO") (pinfunction "~{AD33(SWO/32KHZ})_~AD33/SWO") (pintype "bidirectional"))
    )
    (net (code "57") (name "VCC_1") (class "Default")
      (node (ref "C31") (pin "2") (pinfunction "2_2") (pintype "passive"))
      (node (ref "C32") (pin "1") (pinfunction "1_1") (pintype "passive"))
      (node (ref "C33") (pin "1") (pinfunction "1_1") (pintype "passive"))
      (node (ref "D3") (pin "C") (pinfunction "C_C") (pintype "passive"))
      (node (ref "D6") (pin "C") (pinfunction "C_C") (pintype "passive"))
      (node (ref "R1") (pin "2") (pinfunction "2_2") (pintype "passive"))
      (node (ref "R28") (pin "2") (pinfunction "2_2") (pintype "passive"))
      (node (ref "U8") (pin "VDD@36") (pinfunction "VDD*2_VDD@36") (pintype "bidirectional"))
      (node (ref "U8") (pin "VDD@37") (pinfunction "VDD*2_VDD@37") (pintype "bidirectional"))
    )
    (net (code "58") (name "VIN") (class "Default")
      (node (ref "C1") (pin "1") (pinfunction "1_1") (pintype "passive"))
      (node (ref "JP2") (pin "2") (pinfunction "2_2") (pintype "passive"))
      (node (ref "JP2") (pin "4") (pinfunction "2_4") (pintype "passive"))
      (node (ref "R2") (pin "2") (pinfunction "2_2") (pintype "passive"))
      (node (ref "R7") (pin "2") (pinfunction "2_2") (pintype "passive"))
      (node (ref "U3") (pin "1") (pinfunction "IN_1") (pintype "input"))
      (node (ref "U4") (pin "1") (pinfunction "IN_1") (pintype "input"))
    )
    (net (code "59") (name "VIN{slash}3") (class "Default")
      (node (ref "R6") (pin "2") (pinfunction "2_2") (pintype "passive"))
      (node (ref "R7") (pin "1") (pinfunction "1_1") (pintype "passive"))
      (node (ref "U8") (pin "AD34") (pinfunction "AD34(CMPRF2/PDMDATA)_AD34") (pintype "bidirectional"))
    )
    (net (code "60") (name "VREG_EN") (class "Default")
      (node (ref "J3") (pin "1") (pinfunction "1_1") (pintype "passive"))
      (node (ref "R2") (pin "1") (pinfunction "1_1") (pintype "passive"))
      (node (ref "U3") (pin "3") (pinfunction "EN_3") (pintype "input"))
      (node (ref "VE") (pin "2") (pinfunction "2_2") (pintype "passive"))
    )
    (net (code "61") (name "V_BATT") (class "Default")
      (node (ref "C4") (pin "1") (pinfunction "1_1") (pintype "passive"))
      (node (ref "D1") (pin "A") (pinfunction "A_A") (pintype "passive"))
      (node (ref "J1") (pin "1") (pinfunction "1_1") (pintype "passive"))
      (node (ref "J2") (pin "2") (pinfunction "+_2") (pintype "bidirectional"))
      (node (ref "U2") (pin "3") (pinfunction "VBAT_3") (pintype "power_in"))
    )
    (net (code "62") (name "unconnected-(J2-PAD1-PadNC1)") (class "Default")
      (node (ref "J2") (pin "NC1") (pinfunction "PAD1_NC1") (pintype "bidirectional"))
    )
    (net (code "63") (name "unconnected-(J2-PAD2-PadNC2)") (class "Default")
      (node (ref "J2") (pin "NC2") (pinfunction "PAD2_NC2") (pintype "bidirectional"))
    )
    (net (code "64") (name "unconnected-(U3-NC-Pad4)") (class "Default")
      (node (ref "U3") (pin "4") (pinfunction "NC_4") (pintype "no_connect"))
    )
    (net (code "65") (name "unconnected-(U4-NC-Pad4)") (class "Default")
      (node (ref "U4") (pin "4") (pinfunction "NC_4") (pintype "no_connect"))
    )
    (net (code "66") (name "unconnected-(U8-(ADCD1P{slash}TX1{slash}PDMCLK)D14-PadD14)") (class "Default")
      (node (ref "U8") (pin "D14") (pinfunction "(ADCD1P/TX1/PDMCLK)D14_D14") (pintype "bidirectional"))
    )
    (net (code "67") (name "unconnected-(U8-(BLEIF_IRQ{slash}SWO{slash}I2SWCLK)D41-PadD41)") (class "Default")
      (node (ref "U8") (pin "D41") (pinfunction "(BLEIF_IRQ/SWO/I2SWCLK)D41_D41") (pintype "bidirectional"))
    )
    (net (code "68") (name "unconnected-(U8-(CMPRF1{slash}TRIG1{slash}SCCCLK)D17-PadD17)") (class "Default")
      (node (ref "U8") (pin "D17") (pinfunction "(CMPRF1/TRIG1/SCCCLK)D17_D17") (pintype "bidirectional"))
    )
    (net (code "69") (name "unconnected-(U8-(RX1{slash}TRIG1{slash}PDMDATA)D36-PadD36)") (class "Default")
      (node (ref "U8") (pin "D36") (pinfunction "(RX1/TRIG1/PDMDATA)D36_D36") (pintype "bidirectional"))
    )
    (net (code "70") (name "unconnected-(U8-(SCL3{slash}SCK3{slash}TX1)~{D42}-Pad~D42)") (class "Default")
      (node (ref "U8") (pin "~D42") (pinfunction "(SCL3/SCK3/TX1)~{D42}_~D42") (pintype "bidirectional"))
    )
    (net (code "71") (name "unconnected-(U8-(SCL4{slash}SCK4{slash}TX1)~{D39}-Pad~D39)") (class "Default")
      (node (ref "U8") (pin "~D39") (pinfunction "(SCL4/SCK4/TX1)~{D39}_~D39") (pintype "bidirectional"))
    )
    (net (code "72") (name "unconnected-(U8-(SDA3{slash}SDI3{slash}RX1)~{D43}-Pad~D43)") (class "Default")
      (node (ref "U8") (pin "~D43") (pinfunction "(SDA3/SDI3/RX1)~{D43}_~D43") (pintype "bidirectional"))
    )
    (net (code "73") (name "unconnected-(U8-(SDA4{slash}SDI4{slash}RX1)D40-PadD40)") (class "Default")
      (node (ref "U8") (pin "D40") (pinfunction "(SDA4/SDI4/RX1)D40_D40") (pintype "bidirectional"))
    )
    (net (code "74") (name "unconnected-(U8-(SDO1{slash}TX1{slash}PDMCLK)D10-PadD10)") (class "Default")
      (node (ref "U8") (pin "D10") (pinfunction "(SDO1/TX1/PDMCLK)D10_D10") (pintype "bidirectional"))
    )
    (net (code "75") (name "unconnected-(U8-(SDO2{slash}I2SWCLK)~{D28}-Pad~D28)") (class "Default")
      (node (ref "U8") (pin "~D28") (pinfunction "(SDO2/I2SWCLK)~{D28}_~D28") (pintype "bidirectional"))
    )
    (net (code "76") (name "unconnected-(U8-(SDO3{slash}RX1)D38-PadD38)") (class "Default")
      (node (ref "U8") (pin "D38") (pinfunction "(SDO3/RX1)D38_D38") (pintype "bidirectional"))
    )
    (net (code "77") (name "unconnected-(U8-(SLSCK{slash}SLSCL{slash}CLKOUT)D0-PadD0)") (class "Default")
      (node (ref "U8") (pin "D0") (pinfunction "(SLSCK/SLSCL/CLKOUT)D0_D0") (pintype "bidirectional"))
    )
    (net (code "78") (name "unconnected-(U8-(SLSDI)D2-PadD2)") (class "Default")
      (node (ref "U8") (pin "D2") (pinfunction "(SLSDI)D2_D2") (pintype "bidirectional"))
    )
    (net (code "79") (name "unconnected-(U8-(SLSDO{slash}SLSDA)D1-PadD1)") (class "Default")
      (node (ref "U8") (pin "D1") (pinfunction "(SLSDO/SLSDA)D1_D1") (pintype "bidirectional"))
    )
    (net (code "80") (name "unconnected-(U8-(SWO{slash}I2SDAT{slash}PDMDATA)~{D45}-Pad~D45)") (class "Default")
      (node (ref "U8") (pin "~D45") (pinfunction "(SWO/I2SDAT/PDMDATA)~{D45}_~D45") (pintype "bidirectional"))
    )
    (net (code "81") (name "unconnected-(U8-(TX1{slash}32KHZ{slash}SWO)~{D24}-Pad~D24)") (class "Default")
      (node (ref "U8") (pin "~D24") (pinfunction "(TX1/32KHZ/SWO)~{D24}_~D24") (pintype "bidirectional"))
    )
    (net (code "82") (name "unconnected-(U8-AD16(TRIG0{slash}SCCRST)-PadAD16)") (class "Default")
      (node (ref "U8") (pin "AD16") (pinfunction "AD16(TRIG0/SCCRST)_AD16") (pintype "bidirectional"))
    )
    (net (code "83") (name "unconnected-(U8-~{AD31(SCCCLK})-Pad~AD31)") (class "Default")
      (node (ref "U8") (pin "~AD31") (pinfunction "~{AD31(SCCCLK})_~AD31") (pintype "bidirectional"))
    )
    (net (code "84") (name "unconnected-(U8-~{AD35(TX1{slash}I2SDAT{slash}PDMCLK})-Pad~AD35)") (class "Default")
      (node (ref "U8") (pin "~AD35") (pinfunction "~{AD35(TX1/I2SDAT/PDMCLK})_~AD35") (pintype "bidirectional"))
    )
    (net (code "85") (name "unconnected-(U10-TNOW-Pad6)") (class "Default")
      (node (ref "U10") (pin "6") (pinfunction "TNOW_6") (pintype "bidirectional"))
    )
    (net (code "86") (name "unconnected-(U10-~{CTS}-Pad5)") (class "Default")
      (node (ref "U10") (pin "5") (pinfunction "~{CTS}_5") (pintype "bidirectional"))
    )
    (net (code "87") (name "unconnected-(U13-AUX_CL-Pad7)") (class "Default")
      (node (ref "U13") (pin "7") (pinfunction "AUX_CL_7") (pintype "bidirectional"))
    )
    (net (code "88") (name "unconnected-(U13-AUX_DA-Pad21)") (class "Default")
      (node (ref "U13") (pin "21") (pinfunction "AUX_DA_21") (pintype "bidirectional"))
    )
    (net (code "89") (name "unconnected-(U13-FSYNC-Pad11)") (class "Default")
      (node (ref "U13") (pin "11") (pinfunction "FSYNC_11") (pintype "bidirectional"))
    )
    (net (code "90") (name "unconnected-(U14-NC-Pad4)") (class "Default")
      (node (ref "U14") (pin "4") (pinfunction "NC_4") (pintype "no_connect"))
    )
  )
)
